# PCB_INTER.net
KiCad netlist of a schematic drawn in Altium Designer
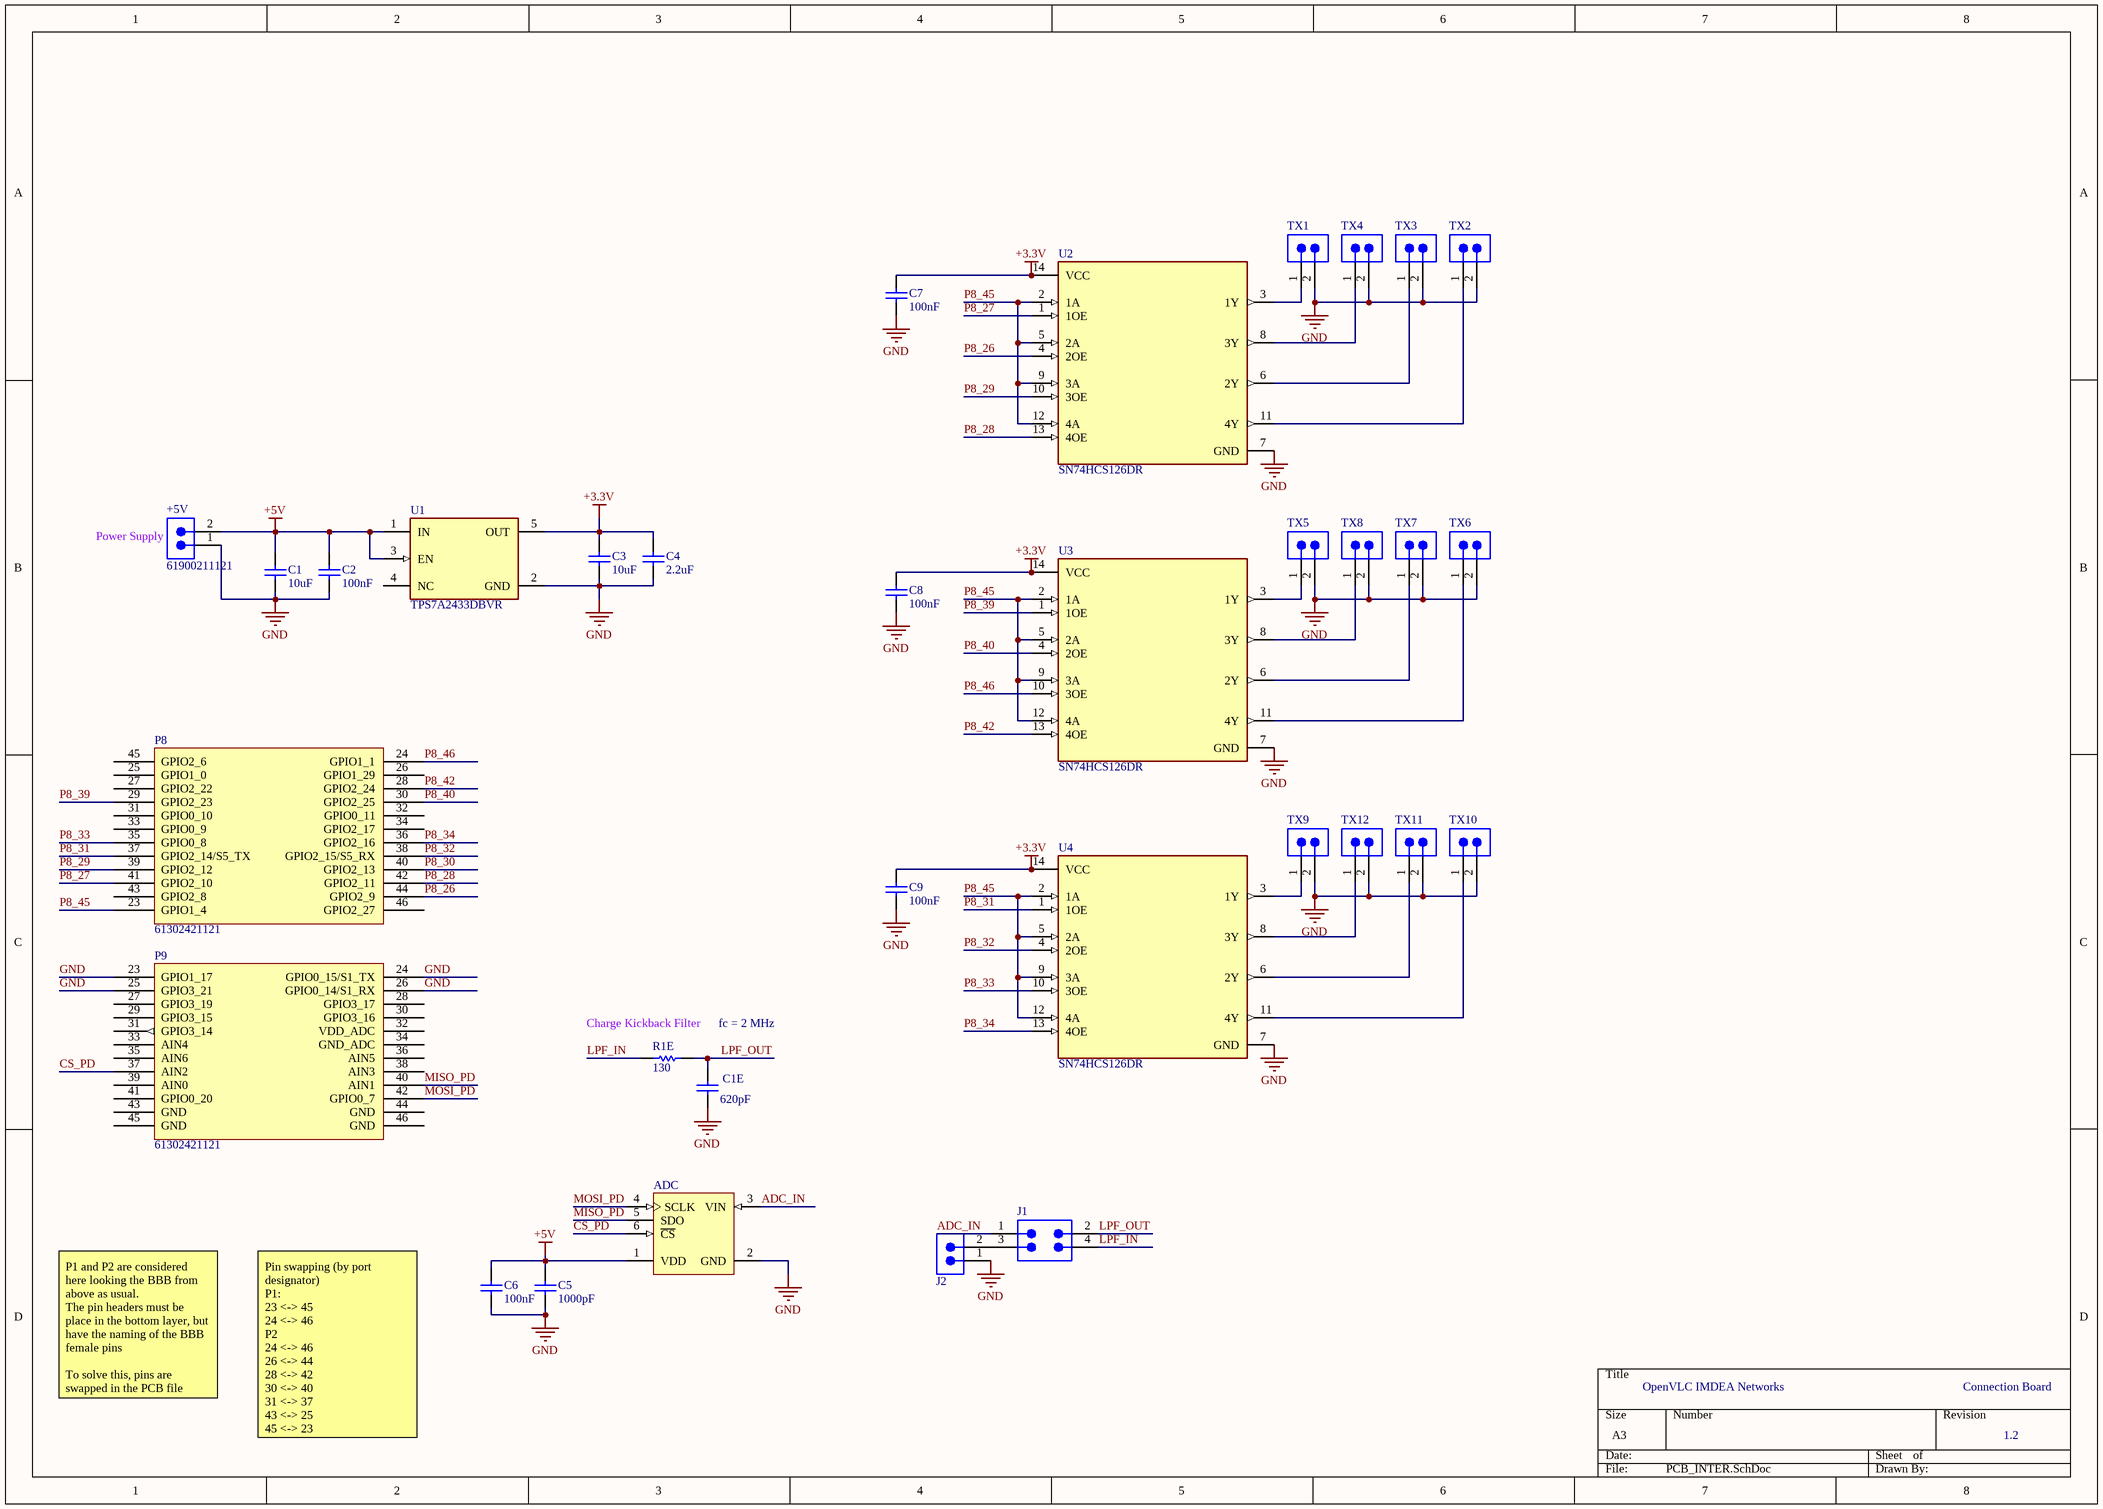
[diagram p0: PCB_INTER.SchDoc]

(export (version "E")
  (design (tool "Eeschema 10.0.6"))
  (components
    (comp (ref "+5V")
      (value "61900211121")
      (footprint "61900211121")
      (libsource (lib "Altium Content Vault") (part "Header_Male_1R_02P"))
    )
    (comp (ref "ADC")
      (value "ADS7886SBDBVR")
      (footprint "TI-DBV6_M")
      (fields (field (name "MANUFACTURER") "Texas Instruments"))
      (libsource (lib "Altium Content Vault") (part "TI-ADS788XDXX6"))
    )
    (comp (ref "C1")
      (value "10uF")
      (footprint "RESC1608X55N")
      (description "Capacitor")
      (fields (field (name "Comment") "GRM188R6YA106MA73D") (field (name "PUBLISHER") "Altium Limited"))
      (libsource (lib "Miscellaneous Devices") (part "Cap"))
    )
    (comp (ref "C1E")
      (value "620pF")
      (footprint "RESC1608X55N")
      (description "Capacitor")
      (fields (field (name "Comment") "Cap") (field (name "PUBLISHER") "Altium Limited"))
      (libsource (lib "Miscellaneous Devices") (part "Cap"))
    )
    (comp (ref "C2")
      (value "100nF")
      (footprint "RESC1608X55N")
      (description "Capacitor")
      (fields (field (name "Comment") "GCM188R71H104KA57J") (field (name "PUBLISHER") "Altium Limited"))
      (libsource (lib "Miscellaneous Devices") (part "Cap"))
    )
    (comp (ref "C3")
      (value "10uF")
      (footprint "RESC1608X55N")
      (description "Capacitor")
      (fields (field (name "Comment") "GRM188R6YA106MA73D") (field (name "PUBLISHER") "Altium Limited"))
      (libsource (lib "Miscellaneous Devices") (part "Cap"))
    )
    (comp (ref "C4")
      (value "2.2uF")
      (footprint "RESC1608X55N")
      (description "Capacitor")
      (fields (field (name "Comment") "GCM188R71H104KA57J") (field (name "PUBLISHER") "Altium Limited"))
      (libsource (lib "Miscellaneous Devices") (part "Cap"))
    )
    (comp (ref "C5")
      (value "1000pF")
      (footprint "RESC1608X55N")
      (description "Capacitor")
      (fields (field (name "Comment") "Cap") (field (name "PUBLISHER") "Altium Limited"))
      (libsource (lib "Miscellaneous Devices") (part "Cap"))
    )
    (comp (ref "C6")
      (value "100nF")
      (footprint "RESC1608X55N")
      (description "Capacitor")
      (fields (field (name "Comment") "Cap") (field (name "PUBLISHER") "Altium Limited"))
      (libsource (lib "Miscellaneous Devices") (part "Cap"))
    )
    (comp (ref "C7")
      (value "100nF")
      (footprint "RESC1608X55N")
      (description "Capacitor")
      (fields (field (name "Comment") "GCM188R71H104KA57J") (field (name "PUBLISHER") "Altium Limited"))
      (libsource (lib "Miscellaneous Devices") (part "Cap"))
    )
    (comp (ref "C8")
      (value "100nF")
      (footprint "RESC1608X55N")
      (description "Capacitor")
      (fields (field (name "Comment") "GCM188R71H104KA57J") (field (name "PUBLISHER") "Altium Limited"))
      (libsource (lib "Miscellaneous Devices") (part "Cap"))
    )
    (comp (ref "C9")
      (value "100nF")
      (footprint "RESC1608X55N")
      (description "Capacitor")
      (fields (field (name "Comment") "GCM188R71H104KA57J") (field (name "PUBLISHER") "Altium Limited"))
      (libsource (lib "Miscellaneous Devices") (part "Cap"))
    )
    (comp (ref "J1")
      (value "61300421121")
      (footprint "61300421121")
      (libsource (lib "Altium Content Vault") (part "Header_Male_2R_04P"))
    )
    (comp (ref "J2")
      (value "61900211121")
      (footprint "61900211121")
      (libsource (lib "Altium Content Vault") (part "Header_Male_1R_02P"))
    )
    (comp (ref "P8")
      (value "61302421121")
      (footprint "BBB_CAPE_NO_HEADER_R_24")
      (libsource (lib "BeagleBoneCape") (part "BBB_P8_reduced"))
    )
    (comp (ref "P9")
      (value "61302421121")
      (footprint "BBB_CAPE_NO_HEADER_R_24")
      (libsource (lib "BeagleBoneCape") (part "BBB_P9_reduced"))
    )
    (comp (ref "R1E")
      (value "130")
      (footprint "RESC1608X55N")
      (description "Resistor")
      (fields (field (name "Comment") "Res1") (field (name "PUBLISHER") "Altium Limited"))
      (libsource (lib "Miscellaneous Devices") (part "Res1"))
    )
    (comp (ref "TX1")
      (value "61900211121")
      (footprint "61900211121")
      (libsource (lib "Altium Content Vault") (part "Header_Male_1R_02P"))
    )
    (comp (ref "TX2")
      (value "61900211121")
      (footprint "61900211121")
      (libsource (lib "Altium Content Vault") (part "Header_Male_1R_02P"))
    )
    (comp (ref "TX3")
      (value "61900211121")
      (footprint "61900211121")
      (libsource (lib "Altium Content Vault") (part "Header_Male_1R_02P"))
    )
    (comp (ref "TX4")
      (value "61900211121")
      (footprint "61900211121")
      (libsource (lib "Altium Content Vault") (part "Header_Male_1R_02P"))
    )
    (comp (ref "TX5")
      (value "61900211121")
      (footprint "61900211121")
      (libsource (lib "Altium Content Vault") (part "Header_Male_1R_02P"))
    )
    (comp (ref "TX6")
      (value "61900211121")
      (footprint "61900211121")
      (libsource (lib "Altium Content Vault") (part "Header_Male_1R_02P"))
    )
    (comp (ref "TX7")
      (value "61900211121")
      (footprint "61900211121")
      (libsource (lib "Altium Content Vault") (part "Header_Male_1R_02P"))
    )
    (comp (ref "TX8")
      (value "61900211121")
      (footprint "61900211121")
      (libsource (lib "Altium Content Vault") (part "Header_Male_1R_02P"))
    )
    (comp (ref "TX9")
      (value "61900211121")
      (footprint "61900211121")
      (libsource (lib "Altium Content Vault") (part "Header_Male_1R_02P"))
    )
    (comp (ref "TX10")
      (value "61900211121")
      (footprint "61900211121")
      (libsource (lib "Altium Content Vault") (part "Header_Male_1R_02P"))
    )
    (comp (ref "TX11")
      (value "61900211121")
      (footprint "61900211121")
      (libsource (lib "Altium Content Vault") (part "Header_Male_1R_02P"))
    )
    (comp (ref "TX12")
      (value "61900211121")
      (footprint "61900211121")
      (libsource (lib "Altium Content Vault") (part "Header_Male_1R_02P"))
    )
    (comp (ref "U1")
      (value "TPS7A2433DBVR")
      (footprint "FP-DBV0005A-MFG")
      (libsource (lib "Altium Content Vault") (part "ee7747973c1ed1d4cccbb20406fa51c"))
    )
    (comp (ref "U2")
      (value "SN74HCS126DR")
      (footprint "FP-D0014A-IPC_A")
      (description "Schmitt-trigger inputs quadruple bus buffer gates with 3-state outputs 14-SOIC -40 to 125")
      (libsource (lib "Altium Content Vault") (part "05e233a5d9b92157a3b307a9d32e8d9"))
    )
    (comp (ref "U3")
      (value "SN74HCS126DR")
      (footprint "FP-D0014A-IPC_A")
      (description "Schmitt-trigger inputs quadruple bus buffer gates with 3-state outputs 14-SOIC -40 to 125")
      (libsource (lib "Altium Content Vault") (part "05e233a5d9b92157a3b307a9d32e8d9"))
    )
    (comp (ref "U4")
      (value "SN74HCS126DR")
      (footprint "FP-D0014A-IPC_A")
      (description "Schmitt-trigger inputs quadruple bus buffer gates with 3-state outputs 14-SOIC -40 to 125")
      (libsource (lib "Altium Content Vault") (part "05e233a5d9b92157a3b307a9d32e8d9"))
    )
  )
  (nets
    (net (code "1") (name "+3.3V") (class "Default")
      (node (ref "C3") (pin "2") (pinfunction "2_2") (pintype "passive"))
      (node (ref "C4") (pin "1") (pinfunction "1_1") (pintype "passive"))
      (node (ref "C7") (pin "1") (pinfunction "1_1") (pintype "passive"))
      (node (ref "C8") (pin "1") (pinfunction "1_1") (pintype "passive"))
      (node (ref "C9") (pin "1") (pinfunction "1_1") (pintype "passive"))
      (node (ref "U1") (pin "5") (pinfunction "OUT_5") (pintype "power_in"))
      (node (ref "U2") (pin "14") (pinfunction "VCC_14") (pintype "power_in"))
      (node (ref "U3") (pin "14") (pinfunction "VCC_14") (pintype "power_in"))
      (node (ref "U4") (pin "14") (pinfunction "VCC_14") (pintype "power_in"))
    )
    (net (code "2") (name "+5V") (class "Default")
      (node (ref "+5V") (pin "2") (pinfunction "2_2") (pintype "passive"))
      (node (ref "ADC") (pin "1") (pinfunction "VDD_1") (pintype "power_in"))
      (node (ref "C1") (pin "1") (pinfunction "1_1") (pintype "passive"))
      (node (ref "C2") (pin "1") (pinfunction "1_1") (pintype "passive"))
      (node (ref "C5") (pin "1") (pinfunction "1_1") (pintype "passive"))
      (node (ref "C6") (pin "1") (pinfunction "1_1") (pintype "passive"))
      (node (ref "U1") (pin "1") (pinfunction "IN_1") (pintype "power_in"))
      (node (ref "U1") (pin "3") (pinfunction "EN_3") (pintype "input"))
    )
    (net (code "3") (name "/ADC_IN") (class "Default")
      (node (ref "ADC") (pin "3") (pinfunction "VIN_3") (pintype "input"))
      (node (ref "J1") (pin "1") (pinfunction "1_1") (pintype "passive"))
    )
    (net (code "4") (name "/CS_PD") (class "Default")
      (node (ref "ADC") (pin "6") (pinfunction "~{CS}_6") (pintype "input"))
      (node (ref "P9") (pin "37") (pinfunction "AIN2_37") (pintype "passive"))
    )
    (net (code "5") (name "/LPF_IN") (class "Default")
      (node (ref "J1") (pin "4") (pinfunction "4_4") (pintype "passive"))
      (node (ref "R1E") (pin "2") (pinfunction "2_2") (pintype "passive"))
    )
    (net (code "6") (name "/LPF_OUT") (class "Default")
      (node (ref "C1E") (pin "1") (pinfunction "1_1") (pintype "passive"))
      (node (ref "J1") (pin "2") (pinfunction "2_2") (pintype "passive"))
      (node (ref "R1E") (pin "1") (pinfunction "1_1") (pintype "passive"))
    )
    (net (code "7") (name "/MISO_PD") (class "Default")
      (node (ref "ADC") (pin "5") (pinfunction "SDO_5") (pintype "tri_state"))
      (node (ref "P9") (pin "40") (pinfunction "AIN1_40") (pintype "passive"))
    )
    (net (code "8") (name "/MOSI_PD") (class "Default")
      (node (ref "ADC") (pin "4") (pinfunction "SCLK_4") (pintype "input"))
      (node (ref "P9") (pin "42") (pinfunction "GPIO0_7_42") (pintype "passive"))
    )
    (net (code "9") (name "/P8_26") (class "Default")
      (node (ref "P8") (pin "44") (pinfunction "GPIO2_9_44") (pintype "passive"))
      (node (ref "U2") (pin "4") (pinfunction "2OE_4") (pintype "input"))
    )
    (net (code "10") (name "/P8_27") (class "Default")
      (node (ref "P8") (pin "41") (pinfunction "GPIO2_10_41") (pintype "passive"))
      (node (ref "U2") (pin "1") (pinfunction "1OE_1") (pintype "input"))
    )
    (net (code "11") (name "/P8_28") (class "Default")
      (node (ref "P8") (pin "42") (pinfunction "GPIO2_11_42") (pintype "passive"))
      (node (ref "U2") (pin "13") (pinfunction "4OE_13") (pintype "input"))
    )
    (net (code "12") (name "/P8_29") (class "Default")
      (node (ref "P8") (pin "39") (pinfunction "GPIO2_12_39") (pintype "passive"))
      (node (ref "U2") (pin "10") (pinfunction "3OE_10") (pintype "input"))
    )
    (net (code "13") (name "/P8_30") (class "Default")
      (node (ref "P8") (pin "40") (pinfunction "GPIO2_13_40") (pintype "passive"))
    )
    (net (code "14") (name "/P8_31") (class "Default")
      (node (ref "P8") (pin "37") (pinfunction "GPIO2_14/S5_TX_37") (pintype "passive"))
      (node (ref "U4") (pin "1") (pinfunction "1OE_1") (pintype "input"))
    )
    (net (code "15") (name "/P8_32") (class "Default")
      (node (ref "P8") (pin "38") (pinfunction "GPIO2_15/S5_RX_38") (pintype "passive"))
      (node (ref "U4") (pin "4") (pinfunction "2OE_4") (pintype "input"))
    )
    (net (code "16") (name "/P8_33") (class "Default")
      (node (ref "P8") (pin "35") (pinfunction "GPIO0_8_35") (pintype "passive"))
      (node (ref "U4") (pin "10") (pinfunction "3OE_10") (pintype "input"))
    )
    (net (code "17") (name "/P8_34") (class "Default")
      (node (ref "P8") (pin "36") (pinfunction "GPIO2_16_36") (pintype "passive"))
      (node (ref "U4") (pin "13") (pinfunction "4OE_13") (pintype "input"))
    )
    (net (code "18") (name "/P8_39") (class "Default")
      (node (ref "P8") (pin "29") (pinfunction "GPIO2_23_29") (pintype "passive"))
      (node (ref "U3") (pin "1") (pinfunction "1OE_1") (pintype "input"))
    )
    (net (code "19") (name "/P8_40") (class "Default")
      (node (ref "P8") (pin "30") (pinfunction "GPIO2_25_30") (pintype "passive"))
      (node (ref "U3") (pin "4") (pinfunction "2OE_4") (pintype "input"))
    )
    (net (code "20") (name "/P8_42") (class "Default")
      (node (ref "P8") (pin "28") (pinfunction "GPIO2_24_28") (pintype "passive"))
      (node (ref "U3") (pin "13") (pinfunction "4OE_13") (pintype "input"))
    )
    (net (code "21") (name "/P8_45") (class "Default")
      (node (ref "P8") (pin "23") (pinfunction "GPIO1_4_23") (pintype "passive"))
      (node (ref "U2") (pin "12") (pinfunction "4A_12") (pintype "input"))
      (node (ref "U2") (pin "2") (pinfunction "1A_2") (pintype "input"))
      (node (ref "U2") (pin "5") (pinfunction "2A_5") (pintype "input"))
      (node (ref "U2") (pin "9") (pinfunction "3A_9") (pintype "input"))
      (node (ref "U3") (pin "12") (pinfunction "4A_12") (pintype "input"))
      (node (ref "U3") (pin "2") (pinfunction "1A_2") (pintype "input"))
      (node (ref "U3") (pin "5") (pinfunction "2A_5") (pintype "input"))
      (node (ref "U3") (pin "9") (pinfunction "3A_9") (pintype "input"))
      (node (ref "U4") (pin "12") (pinfunction "4A_12") (pintype "input"))
      (node (ref "U4") (pin "2") (pinfunction "1A_2") (pintype "input"))
      (node (ref "U4") (pin "5") (pinfunction "2A_5") (pintype "input"))
      (node (ref "U4") (pin "9") (pinfunction "3A_9") (pintype "input"))
    )
    (net (code "22") (name "/P8_46") (class "Default")
      (node (ref "P8") (pin "24") (pinfunction "GPIO1_1_24") (pintype "passive"))
      (node (ref "U3") (pin "10") (pinfunction "3OE_10") (pintype "input"))
    )
    (net (code "23") (name "GND") (class "Default")
      (node (ref "+5V") (pin "1") (pinfunction "1_1") (pintype "passive"))
      (node (ref "ADC") (pin "2") (pinfunction "GND_2") (pintype "power_in"))
      (node (ref "C1") (pin "2") (pinfunction "2_2") (pintype "passive"))
      (node (ref "C1E") (pin "2") (pinfunction "2_2") (pintype "passive"))
      (node (ref "C2") (pin "2") (pinfunction "2_2") (pintype "passive"))
      (node (ref "C3") (pin "1") (pinfunction "1_1") (pintype "passive"))
      (node (ref "C4") (pin "2") (pinfunction "2_2") (pintype "passive"))
      (node (ref "C5") (pin "2") (pinfunction "2_2") (pintype "passive"))
      (node (ref "C6") (pin "2") (pinfunction "2_2") (pintype "passive"))
      (node (ref "C7") (pin "2") (pinfunction "2_2") (pintype "passive"))
      (node (ref "C8") (pin "2") (pinfunction "2_2") (pintype "passive"))
      (node (ref "C9") (pin "2") (pinfunction "2_2") (pintype "passive"))
      (node (ref "J2") (pin "1") (pinfunction "1_1") (pintype "passive"))
      (node (ref "P9") (pin "23") (pinfunction "GPIO1_17_23") (pintype "passive"))
      (node (ref "P9") (pin "24") (pinfunction "GPIO0_15/S1_TX_24") (pintype "passive"))
      (node (ref "P9") (pin "25") (pinfunction "GPIO3_21_25") (pintype "passive"))
      (node (ref "P9") (pin "26") (pinfunction "GPIO0_14/S1_RX_26") (pintype "passive"))
      (node (ref "TX1") (pin "2") (pinfunction "2_2") (pintype "passive"))
      (node (ref "TX10") (pin "2") (pinfunction "2_2") (pintype "passive"))
      (node (ref "TX11") (pin "2") (pinfunction "2_2") (pintype "passive"))
      (node (ref "TX12") (pin "2") (pinfunction "2_2") (pintype "passive"))
      (node (ref "TX2") (pin "2") (pinfunction "2_2") (pintype "passive"))
      (node (ref "TX3") (pin "2") (pinfunction "2_2") (pintype "passive"))
      (node (ref "TX4") (pin "2") (pinfunction "2_2") (pintype "passive"))
      (node (ref "TX5") (pin "2") (pinfunction "2_2") (pintype "passive"))
      (node (ref "TX6") (pin "2") (pinfunction "2_2") (pintype "passive"))
      (node (ref "TX7") (pin "2") (pinfunction "2_2") (pintype "passive"))
      (node (ref "TX8") (pin "2") (pinfunction "2_2") (pintype "passive"))
      (node (ref "TX9") (pin "2") (pinfunction "2_2") (pintype "passive"))
      (node (ref "U1") (pin "2") (pinfunction "GND_2") (pintype "power_in"))
      (node (ref "U2") (pin "7") (pinfunction "GND_7") (pintype "power_in"))
      (node (ref "U3") (pin "7") (pinfunction "GND_7") (pintype "power_in"))
      (node (ref "U4") (pin "7") (pinfunction "GND_7") (pintype "power_in"))
    )
    (net (code "24") (name "Net-(J1-Pad3)") (class "Default")
      (node (ref "J1") (pin "3") (pinfunction "3_3") (pintype "passive"))
      (node (ref "J2") (pin "2") (pinfunction "2_2") (pintype "passive"))
    )
    (net (code "25") (name "Net-(U2-1Y)") (class "Default")
      (node (ref "TX1") (pin "1") (pinfunction "1_1") (pintype "passive"))
      (node (ref "U2") (pin "3") (pinfunction "1Y_3") (pintype "output"))
    )
    (net (code "26") (name "Net-(U2-2Y)") (class "Default")
      (node (ref "TX3") (pin "1") (pinfunction "1_1") (pintype "passive"))
      (node (ref "U2") (pin "6") (pinfunction "2Y_6") (pintype "output"))
    )
    (net (code "27") (name "Net-(U2-3Y)") (class "Default")
      (node (ref "TX4") (pin "1") (pinfunction "1_1") (pintype "passive"))
      (node (ref "U2") (pin "8") (pinfunction "3Y_8") (pintype "output"))
    )
    (net (code "28") (name "Net-(U2-4Y)") (class "Default")
      (node (ref "TX2") (pin "1") (pinfunction "1_1") (pintype "passive"))
      (node (ref "U2") (pin "11") (pinfunction "4Y_11") (pintype "output"))
    )
    (net (code "29") (name "Net-(U3-1Y)") (class "Default")
      (node (ref "TX5") (pin "1") (pinfunction "1_1") (pintype "passive"))
      (node (ref "U3") (pin "3") (pinfunction "1Y_3") (pintype "output"))
    )
    (net (code "30") (name "Net-(U3-2Y)") (class "Default")
      (node (ref "TX7") (pin "1") (pinfunction "1_1") (pintype "passive"))
      (node (ref "U3") (pin "6") (pinfunction "2Y_6") (pintype "output"))
    )
    (net (code "31") (name "Net-(U3-3Y)") (class "Default")
      (node (ref "TX8") (pin "1") (pinfunction "1_1") (pintype "passive"))
      (node (ref "U3") (pin "8") (pinfunction "3Y_8") (pintype "output"))
    )
    (net (code "32") (name "Net-(U3-4Y)") (class "Default")
      (node (ref "TX6") (pin "1") (pinfunction "1_1") (pintype "passive"))
      (node (ref "U3") (pin "11") (pinfunction "4Y_11") (pintype "output"))
    )
    (net (code "33") (name "Net-(U4-1Y)") (class "Default")
      (node (ref "TX9") (pin "1") (pinfunction "1_1") (pintype "passive"))
      (node (ref "U4") (pin "3") (pinfunction "1Y_3") (pintype "output"))
    )
    (net (code "34") (name "Net-(U4-2Y)") (class "Default")
      (node (ref "TX11") (pin "1") (pinfunction "1_1") (pintype "passive"))
      (node (ref "U4") (pin "6") (pinfunction "2Y_6") (pintype "output"))
    )
    (net (code "35") (name "Net-(U4-3Y)") (class "Default")
      (node (ref "TX12") (pin "1") (pinfunction "1_1") (pintype "passive"))
      (node (ref "U4") (pin "8") (pinfunction "3Y_8") (pintype "output"))
    )
    (net (code "36") (name "Net-(U4-4Y)") (class "Default")
      (node (ref "TX10") (pin "1") (pinfunction "1_1") (pintype "passive"))
      (node (ref "U4") (pin "11") (pinfunction "4Y_11") (pintype "output"))
    )
    (net (code "37") (name "unconnected-(P8-GPIO0_9-Pad33)") (class "Default")
      (node (ref "P8") (pin "33") (pinfunction "GPIO0_9_33") (pintype "passive"))
    )
    (net (code "38") (name "unconnected-(P8-GPIO0_10-Pad31)") (class "Default")
      (node (ref "P8") (pin "31") (pinfunction "GPIO0_10_31") (pintype "passive"))
    )
    (net (code "39") (name "unconnected-(P8-GPIO0_11-Pad32)") (class "Default")
      (node (ref "P8") (pin "32") (pinfunction "GPIO0_11_32") (pintype "passive"))
    )
    (net (code "40") (name "unconnected-(P8-GPIO1_0-Pad25)") (class "Default")
      (node (ref "P8") (pin "25") (pinfunction "GPIO1_0_25") (pintype "passive"))
    )
    (net (code "41") (name "unconnected-(P8-GPIO1_29-Pad26)") (class "Default")
      (node (ref "P8") (pin "26") (pinfunction "GPIO1_29_26") (pintype "passive"))
    )
    (net (code "42") (name "unconnected-(P8-GPIO2_6-Pad45)") (class "Default")
      (node (ref "P8") (pin "45") (pinfunction "GPIO2_6_45") (pintype "passive"))
    )
    (net (code "43") (name "unconnected-(P8-GPIO2_8-Pad43)") (class "Default")
      (node (ref "P8") (pin "43") (pinfunction "GPIO2_8_43") (pintype "passive"))
    )
    (net (code "44") (name "unconnected-(P8-GPIO2_17-Pad34)") (class "Default")
      (node (ref "P8") (pin "34") (pinfunction "GPIO2_17_34") (pintype "passive"))
    )
    (net (code "45") (name "unconnected-(P8-GPIO2_22-Pad27)") (class "Default")
      (node (ref "P8") (pin "27") (pinfunction "GPIO2_22_27") (pintype "passive"))
    )
    (net (code "46") (name "unconnected-(P8-GPIO2_27-Pad46)") (class "Default")
      (node (ref "P8") (pin "46") (pinfunction "GPIO2_27_46") (pintype "passive"))
    )
    (net (code "47") (name "unconnected-(P9-AIN0-Pad39)") (class "Default")
      (node (ref "P9") (pin "39") (pinfunction "AIN0_39") (pintype "passive"))
    )
    (net (code "48") (name "unconnected-(P9-AIN3-Pad38)") (class "Default")
      (node (ref "P9") (pin "38") (pinfunction "AIN3_38") (pintype "passive"))
    )
    (net (code "49") (name "unconnected-(P9-AIN4-Pad33)") (class "Default")
      (node (ref "P9") (pin "33") (pinfunction "AIN4_33") (pintype "passive"))
    )
    (net (code "50") (name "unconnected-(P9-AIN5-Pad36)") (class "Default")
      (node (ref "P9") (pin "36") (pinfunction "AIN5_36") (pintype "passive"))
    )
    (net (code "51") (name "unconnected-(P9-AIN6-Pad35)") (class "Default")
      (node (ref "P9") (pin "35") (pinfunction "AIN6_35") (pintype "passive"))
    )
    (net (code "52") (name "unconnected-(P9-GND-Pad43)") (class "Default")
      (node (ref "P9") (pin "43") (pinfunction "GND_43") (pintype "passive"))
    )
    (net (code "53") (name "unconnected-(P9-GND-Pad44)") (class "Default")
      (node (ref "P9") (pin "44") (pinfunction "GND_44") (pintype "passive"))
    )
    (net (code "54") (name "unconnected-(P9-GND-Pad45)") (class "Default")
      (node (ref "P9") (pin "45") (pinfunction "GND_45") (pintype "passive"))
    )
    (net (code "55") (name "unconnected-(P9-GND-Pad46)") (class "Default")
      (node (ref "P9") (pin "46") (pinfunction "GND_46") (pintype "passive"))
    )
    (net (code "56") (name "unconnected-(P9-GND_ADC-Pad34)") (class "Default")
      (node (ref "P9") (pin "34") (pinfunction "GND_ADC_34") (pintype "passive"))
    )
    (net (code "57") (name "unconnected-(P9-GPIO0_20-Pad41)") (class "Default")
      (node (ref "P9") (pin "41") (pinfunction "GPIO0_20_41") (pintype "passive"))
    )
    (net (code "58") (name "unconnected-(P9-GPIO3_14-Pad31)") (class "Default")
      (node (ref "P9") (pin "31") (pinfunction "GPIO3_14_31") (pintype "output"))
    )
    (net (code "59") (name "unconnected-(P9-GPIO3_15-Pad29)") (class "Default")
      (node (ref "P9") (pin "29") (pinfunction "GPIO3_15_29") (pintype "passive"))
    )
    (net (code "60") (name "unconnected-(P9-GPIO3_16-Pad30)") (class "Default")
      (node (ref "P9") (pin "30") (pinfunction "GPIO3_16_30") (pintype "passive"))
    )
    (net (code "61") (name "unconnected-(P9-GPIO3_17-Pad28)") (class "Default")
      (node (ref "P9") (pin "28") (pinfunction "GPIO3_17_28") (pintype "passive"))
    )
    (net (code "62") (name "unconnected-(P9-GPIO3_19-Pad27)") (class "Default")
      (node (ref "P9") (pin "27") (pinfunction "GPIO3_19_27") (pintype "passive"))
    )
    (net (code "63") (name "unconnected-(P9-VDD_ADC-Pad32)") (class "Default")
      (node (ref "P9") (pin "32") (pinfunction "VDD_ADC_32") (pintype "passive"))
    )
    (net (code "64") (name "unconnected-(U1-NC-Pad4)") (class "Default")
      (node (ref "U1") (pin "4") (pinfunction "NC_4") (pintype "passive"))
    )
  )
)
